# ECE3400Treasure.net
KiCad netlist of a schematic drawn in EAGLE
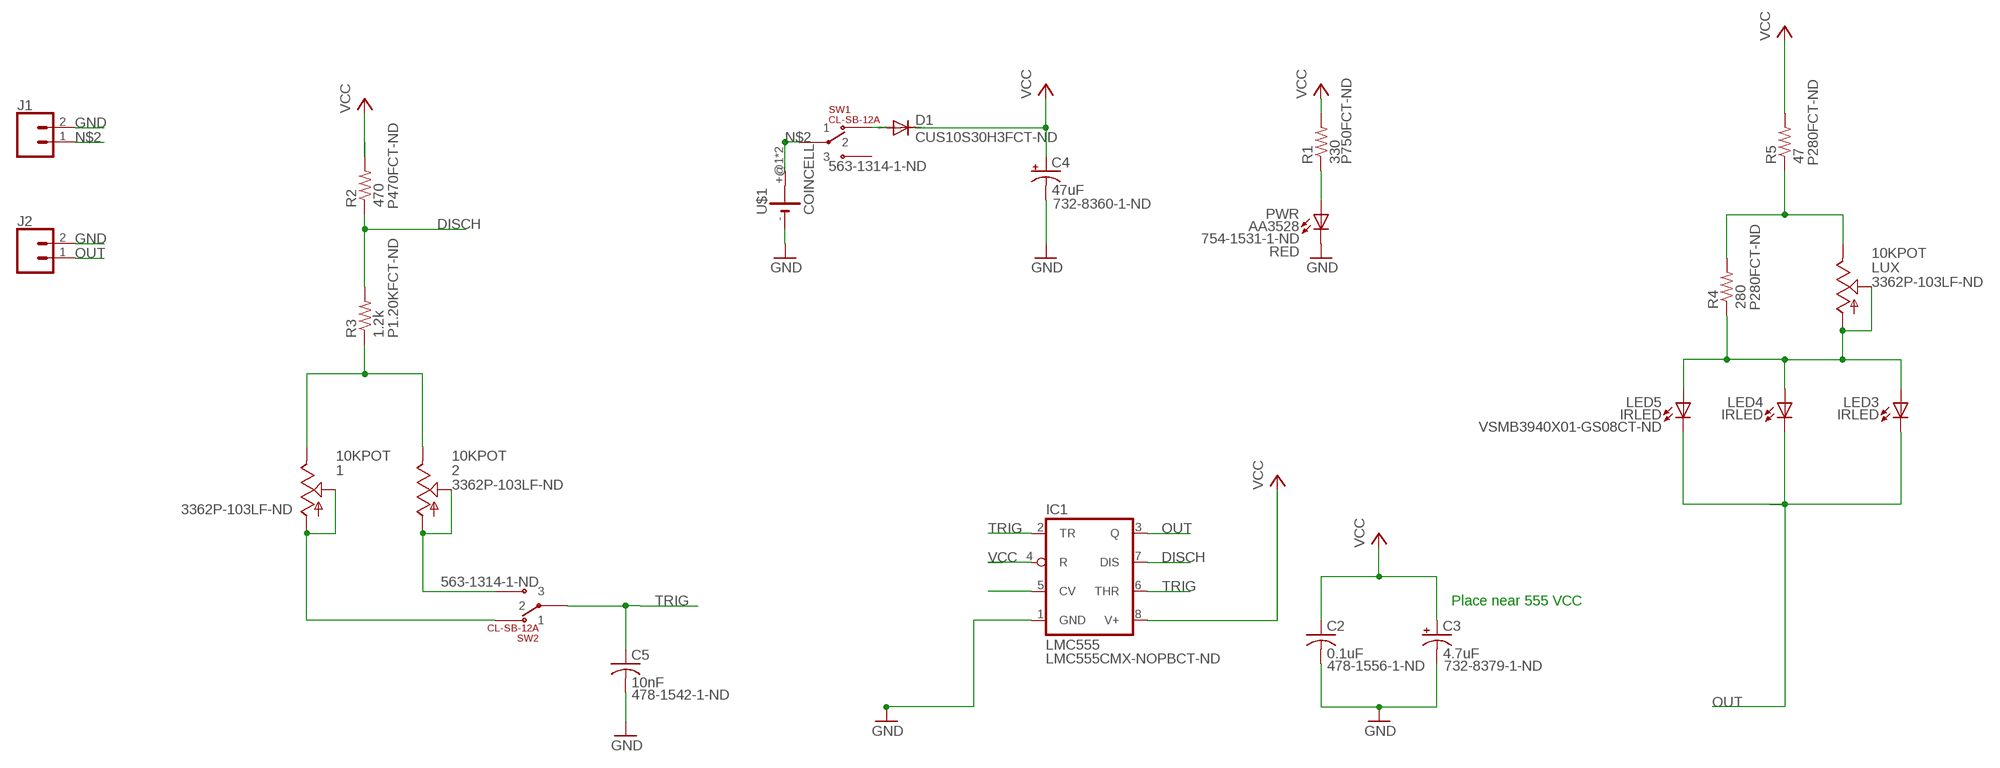
[diagram p0: schematic, sheet 1]

(export (version "E")
  (design (tool "Eeschema 10.0.6"))
  (components
    (comp (ref "1")
      (value "10KPOT")
      (footprint "eagle-import:POT")
      (fields (field (name "DGPN") "3362P-103LF-ND"))
      (libsource (lib "eagle-import") (part "10KPOT"))
    )
    (comp (ref "2")
      (value "10KPOT")
      (footprint "eagle-import:POT")
      (fields (field (name "DGPN") "3362P-103LF-ND"))
      (libsource (lib "eagle-import") (part "10KPOT"))
    )
    (comp (ref "C2")
      (value "0.1uF")
      (footprint "eagle-import:C1206")
      (fields (field (name "DGPN") "478-1556-1-ND"))
      (libsource (lib "eagle-import") (part "C-USC1206"))
    )
    (comp (ref "C3")
      (value "4.7uF")
      (footprint "eagle-import:UD-6,6X6,6")
      (fields (field (name "DGPN") "732-8379-1-ND"))
      (libsource (lib "eagle-import") (part "CPOL"))
    )
    (comp (ref "C4")
      (value "47uF")
      (footprint "eagle-import:UD-6,6X6,6")
      (fields (field (name "DGPN") "732-8360-1-ND"))
      (libsource (lib "eagle-import") (part "CPOL"))
    )
    (comp (ref "C5")
      (value "10nF")
      (footprint "eagle-import:C1206")
      (fields (field (name "DGPN") "478-1542-1-ND"))
      (libsource (lib "eagle-import") (part "C-USC1206"))
    )
    (comp (ref "D1")
      (value "DIODE-SOD323-R")
      (footprint "eagle-import:SOD323-R")
      (fields (field (name "DGPN") "CUS10S30H3FCT-ND "))
      (libsource (lib "eagle-import") (part "DIODE-SOD323-R"))
    )
    (comp (ref "IC1")
      (value "LMC555")
      (footprint "eagle-import:SO08")
      (fields (field (name "DGPN") "LMC555CMX-NOPBCT-ND"))
      (libsource (lib "eagle-import") (part "555DLM"))
    )
    (comp (ref "J1")
      (value "CONN_02")
      (footprint "eagle-import:1X02")
      (libsource (lib "eagle-import") (part "CONN_02"))
    )
    (comp (ref "J2")
      (value "CONN_02")
      (footprint "eagle-import:1X02")
      (libsource (lib "eagle-import") (part "CONN_02"))
    )
    (comp (ref "LED3")
      (value "IRLED")
      (footprint "eagle-import:2-SMD")
      (libsource (lib "eagle-import") (part "IRLED"))
    )
    (comp (ref "LED4")
      (value "IRLED")
      (footprint "eagle-import:2-SMD")
      (libsource (lib "eagle-import") (part "IRLED"))
    )
    (comp (ref "LED5")
      (value "IRLED")
      (footprint "eagle-import:2-SMD")
      (fields (field (name "DGPN") "VSMB3940X01-GS08CT-ND"))
      (libsource (lib "eagle-import") (part "IRLED"))
    )
    (comp (ref "LUX")
      (value "10KPOT")
      (footprint "eagle-import:POT")
      (fields (field (name "DGPN") "3362P-103LF-ND"))
      (libsource (lib "eagle-import") (part "10KPOT"))
    )
    (comp (ref "PWR")
      (value "AA3528")
      (footprint "eagle-import:2-PLCC")
      (fields (field (name "COLOR") "RED") (field (name "DGPN") "754-1531-1-ND"))
      (libsource (lib "eagle-import") (part "AA3528"))
    )
    (comp (ref "R1")
      (value "330")
      (footprint "eagle-import:R1206")
      (fields (field (name "DGPN") "P750FCT-ND"))
      (libsource (lib "eagle-import") (part "R-US_R1206"))
    )
    (comp (ref "R2")
      (value "470")
      (footprint "eagle-import:R1206")
      (fields (field (name "DGPN") "P470FCT-ND"))
      (libsource (lib "eagle-import") (part "R-US_R1206"))
    )
    (comp (ref "R3")
      (value "1.2k")
      (footprint "eagle-import:R1206")
      (fields (field (name "DGPN") "P1.20KFCT-ND"))
      (libsource (lib "eagle-import") (part "R-US_R1206"))
    )
    (comp (ref "R4")
      (value "280")
      (footprint "eagle-import:R1206")
      (fields (field (name "DGPN") "P280FCT-ND"))
      (libsource (lib "eagle-import") (part "R-US_R1206"))
    )
    (comp (ref "R5")
      (value "47")
      (footprint "eagle-import:R1206")
      (fields (field (name "DGPN") "P280FCT-ND"))
      (libsource (lib "eagle-import") (part "R-US_R1206"))
    )
    (comp (ref "SW1")
      (value "CL-SB-12A")
      (footprint "eagle-import:CL-SB-12A")
      (fields (field (name "DGPN") "563-1314-1-ND"))
      (libsource (lib "eagle-import") (part "CL-SB-12A"))
    )
    (comp (ref "SW2")
      (value "CL-SB-12A")
      (footprint "eagle-import:CL-SB-12A")
      (fields (field (name "DGPN") "563-1314-1-ND"))
      (libsource (lib "eagle-import") (part "CL-SB-12A"))
    )
    (comp (ref "U$1")
      (value "COINCELL")
      (footprint "eagle-import:COINCELL")
      (libsource (lib "eagle-import") (part "COINCELL"))
    )
  )
  (nets
    (net (code "1") (name "/DISCH") (class "Default")
      (node (ref "IC1") (pin "7") (pinfunction "DIS_7") (pintype "input"))
      (node (ref "R2") (pin "1") (pinfunction "1_1") (pintype "passive"))
      (node (ref "R3") (pin "2") (pinfunction "2_2") (pintype "passive"))
    )
    (net (code "2") (name "/N$2") (class "Default")
      (node (ref "J1") (pin "1") (pinfunction "1_1") (pintype "passive"))
      (node (ref "SW1") (pin "1") (pinfunction "2_1") (pintype "bidirectional"))
      (node (ref "U$1") (pin "+@1") (pinfunction "+_+@1") (pintype "passive"))
      (node (ref "U$1") (pin "+@2") (pinfunction "+_+@2") (pintype "passive"))
    )
    (net (code "3") (name "/OUT") (class "Default")
      (node (ref "IC1") (pin "3") (pinfunction "Q_3") (pintype "output"))
      (node (ref "J2") (pin "1") (pinfunction "1_1") (pintype "passive"))
      (node (ref "LED3") (pin "P$2") (pinfunction "C_P$2") (pintype "passive"))
      (node (ref "LED4") (pin "P$2") (pinfunction "C_P$2") (pintype "passive"))
      (node (ref "LED5") (pin "P$2") (pinfunction "C_P$2") (pintype "passive"))
    )
    (net (code "4") (name "/TRIG") (class "Default")
      (node (ref "C5") (pin "1") (pinfunction "1_1") (pintype "passive"))
      (node (ref "IC1") (pin "2") (pinfunction "TR_2") (pintype "input"))
      (node (ref "IC1") (pin "6") (pinfunction "THR_6") (pintype "input"))
      (node (ref "SW2") (pin "1") (pinfunction "2_1") (pintype "bidirectional"))
    )
    (net (code "5") (name "GND") (class "Default")
      (node (ref "C2") (pin "2") (pinfunction "2_2") (pintype "passive"))
      (node (ref "C3") (pin "-") (pinfunction "-_-") (pintype "passive"))
      (node (ref "C4") (pin "-") (pinfunction "-_-") (pintype "passive"))
      (node (ref "C5") (pin "2") (pinfunction "2_2") (pintype "passive"))
      (node (ref "IC1") (pin "1") (pinfunction "GND_1") (pintype "power_in"))
      (node (ref "J1") (pin "2") (pinfunction "2_2") (pintype "passive"))
      (node (ref "J2") (pin "2") (pinfunction "2_2") (pintype "passive"))
      (node (ref "PWR") (pin "P$2") (pinfunction "C_P$2") (pintype "passive"))
      (node (ref "U$1") (pin "-") (pinfunction "-_-") (pintype "passive"))
    )
    (net (code "6") (name "Net-(1-A)") (class "Default")
      (node (ref "1") (pin "P$1") (pinfunction "A_P$1") (pintype "passive"))
      (node (ref "1") (pin "P$2") (pinfunction "S_P$2") (pintype "passive"))
      (node (ref "SW2") (pin "2") (pinfunction "1_2") (pintype "bidirectional"))
    )
    (net (code "7") (name "Net-(1-E)") (class "Default")
      (node (ref "1") (pin "P$3") (pinfunction "E_P$3") (pintype "passive"))
      (node (ref "2") (pin "P$3") (pinfunction "E_P$3") (pintype "passive"))
      (node (ref "R3") (pin "1") (pinfunction "1_1") (pintype "passive"))
    )
    (net (code "8") (name "Net-(2-A)") (class "Default")
      (node (ref "2") (pin "P$1") (pinfunction "A_P$1") (pintype "passive"))
      (node (ref "2") (pin "P$2") (pinfunction "S_P$2") (pintype "passive"))
      (node (ref "SW2") (pin "3") (pinfunction "3_3") (pintype "bidirectional"))
    )
    (net (code "9") (name "Net-(LED3-A)") (class "Default")
      (node (ref "LED3") (pin "P$1") (pinfunction "A_P$1") (pintype "passive"))
      (node (ref "LED4") (pin "P$1") (pinfunction "A_P$1") (pintype "passive"))
      (node (ref "LED5") (pin "P$1") (pinfunction "A_P$1") (pintype "passive"))
      (node (ref "LUX") (pin "P$1") (pinfunction "A_P$1") (pintype "passive"))
      (node (ref "LUX") (pin "P$2") (pinfunction "S_P$2") (pintype "passive"))
      (node (ref "R4") (pin "1") (pinfunction "1_1") (pintype "passive"))
    )
    (net (code "10") (name "Net-(LUX-E)") (class "Default")
      (node (ref "LUX") (pin "P$3") (pinfunction "E_P$3") (pintype "passive"))
      (node (ref "R4") (pin "2") (pinfunction "2_2") (pintype "passive"))
      (node (ref "R5") (pin "1") (pinfunction "1_1") (pintype "passive"))
    )
    (net (code "11") (name "Net-(PWR-A)") (class "Default")
      (node (ref "PWR") (pin "P$1") (pinfunction "A_P$1") (pintype "passive"))
      (node (ref "R1") (pin "1") (pinfunction "1_1") (pintype "passive"))
    )
    (net (code "12") (name "Net-(SW1-1)") (class "Default")
      (node (ref "D1") (pin "A") (pinfunction "A_A") (pintype "passive"))
      (node (ref "SW1") (pin "2") (pinfunction "1_2") (pintype "bidirectional"))
    )
    (net (code "13") (name "VCC") (class "Default")
      (node (ref "C2") (pin "1") (pinfunction "1_1") (pintype "passive"))
      (node (ref "C3") (pin "+") (pinfunction "+_+") (pintype "passive"))
      (node (ref "C4") (pin "+") (pinfunction "+_+") (pintype "passive"))
      (node (ref "D1") (pin "C") (pinfunction "C_C") (pintype "passive"))
      (node (ref "IC1") (pin "4") (pinfunction "R_4") (pintype "input"))
      (node (ref "IC1") (pin "8") (pinfunction "V+_8") (pintype "power_in"))
      (node (ref "R1") (pin "2") (pinfunction "2_2") (pintype "passive"))
      (node (ref "R2") (pin "2") (pinfunction "2_2") (pintype "passive"))
      (node (ref "R5") (pin "2") (pinfunction "2_2") (pintype "passive"))
    )
    (net (code "14") (name "unconnected-(IC1-CV-Pad5)") (class "Default")
      (node (ref "IC1") (pin "5") (pinfunction "CV_5") (pintype "input"))
    )
    (net (code "15") (name "unconnected-(SW1-Pad3)") (class "Default")
      (node (ref "SW1") (pin "3") (pinfunction "3_3") (pintype "bidirectional"))
    )
  )
)
